# JMDuino_Shield.net
KiCad netlist of a schematic drawn in EAGLE
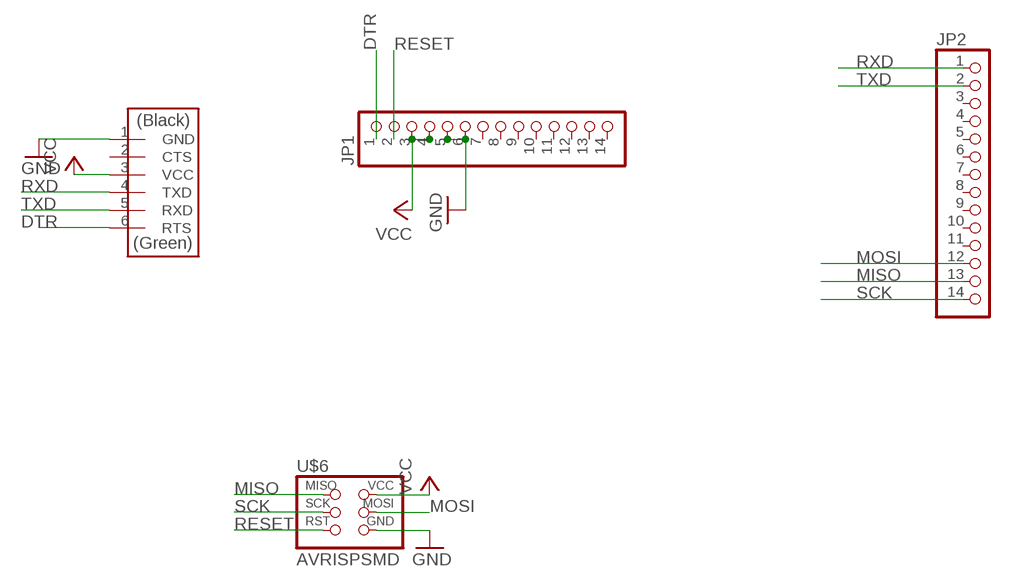
[diagram p0: schematic, sheet 1]

(export (version "E")
  (design (tool "Eeschema 10.0.6"))
  (components
    (comp (ref "JP1")
      (value "PINHD-1X14")
      (footprint "eagle-import:1X14")
      (libsource (lib "eagle-import") (part "PINHD-1X14"))
    )
    (comp (ref "JP2")
      (value "PINHD-1X14")
      (footprint "eagle-import:1X14")
      (libsource (lib "eagle-import") (part "PINHD-1X14"))
    )
    (comp (ref "U$1")
      (value "FTDI-SMD-HEADER")
      (footprint "eagle-import:1X06SMD")
      (libsource (lib "eagle-import") (part "FTDI-SMD-HEADER"))
    )
    (comp (ref "U$6")
      (value "AVRISPSMD")
      (footprint "eagle-import:2X03SMD")
      (libsource (lib "eagle-import") (part "AVRISPSMD"))
    )
  )
  (nets
    (net (code "1") (name "/DTR") (class "Default")
      (node (ref "JP1") (pin "1") (pinfunction "1_1") (pintype "passive"))
      (node (ref "U$1") (pin "6") (pinfunction "RTS_6") (pintype "bidirectional"))
    )
    (net (code "2") (name "/MISO") (class "Default")
      (node (ref "JP2") (pin "13") (pinfunction "13_13") (pintype "passive"))
      (node (ref "U$6") (pin "1") (pinfunction "MISO_1") (pintype "passive"))
    )
    (net (code "3") (name "/MOSI") (class "Default")
      (node (ref "JP2") (pin "12") (pinfunction "12_12") (pintype "passive"))
      (node (ref "U$6") (pin "4") (pinfunction "MOSI_4") (pintype "passive"))
    )
    (net (code "4") (name "/RESET") (class "Default")
      (node (ref "JP1") (pin "2") (pinfunction "2_2") (pintype "passive"))
      (node (ref "U$6") (pin "5") (pinfunction "RST_5") (pintype "passive"))
    )
    (net (code "5") (name "/RXD") (class "Default")
      (node (ref "JP2") (pin "1") (pinfunction "1_1") (pintype "passive"))
      (node (ref "U$1") (pin "4") (pinfunction "TXD_4") (pintype "bidirectional"))
    )
    (net (code "6") (name "/SCK") (class "Default")
      (node (ref "JP2") (pin "14") (pinfunction "14_14") (pintype "passive"))
      (node (ref "U$6") (pin "3") (pinfunction "SCK_3") (pintype "passive"))
    )
    (net (code "7") (name "/TXD") (class "Default")
      (node (ref "JP2") (pin "2") (pinfunction "2_2") (pintype "passive"))
      (node (ref "U$1") (pin "5") (pinfunction "RXD_5") (pintype "bidirectional"))
    )
    (net (code "8") (name "GND") (class "Default")
      (node (ref "JP1") (pin "5") (pinfunction "5_5") (pintype "passive"))
      (node (ref "JP1") (pin "6") (pinfunction "6_6") (pintype "passive"))
      (node (ref "U$1") (pin "1") (pinfunction "GND_1") (pintype "bidirectional"))
      (node (ref "U$6") (pin "6") (pinfunction "GND_6") (pintype "passive"))
    )
    (net (code "9") (name "VCC") (class "Default")
      (node (ref "JP1") (pin "3") (pinfunction "3_3") (pintype "passive"))
      (node (ref "JP1") (pin "4") (pinfunction "4_4") (pintype "passive"))
      (node (ref "U$1") (pin "3") (pinfunction "VCC_3") (pintype "bidirectional"))
      (node (ref "U$6") (pin "2") (pinfunction "VCC_2") (pintype "passive"))
    )
    (net (code "10") (name "unconnected-(JP1-Pad7)") (class "Default")
      (node (ref "JP1") (pin "7") (pinfunction "7_7") (pintype "passive"))
    )
    (net (code "11") (name "unconnected-(JP1-Pad8)") (class "Default")
      (node (ref "JP1") (pin "8") (pinfunction "8_8") (pintype "passive"))
    )
    (net (code "12") (name "unconnected-(JP1-Pad9)") (class "Default")
      (node (ref "JP1") (pin "9") (pinfunction "9_9") (pintype "passive"))
    )
    (net (code "13") (name "unconnected-(JP1-Pad10)") (class "Default")
      (node (ref "JP1") (pin "10") (pinfunction "10_10") (pintype "passive"))
    )
    (net (code "14") (name "unconnected-(JP1-Pad11)") (class "Default")
      (node (ref "JP1") (pin "11") (pinfunction "11_11") (pintype "passive"))
    )
    (net (code "15") (name "unconnected-(JP1-Pad12)") (class "Default")
      (node (ref "JP1") (pin "12") (pinfunction "12_12") (pintype "passive"))
    )
    (net (code "16") (name "unconnected-(JP1-Pad13)") (class "Default")
      (node (ref "JP1") (pin "13") (pinfunction "13_13") (pintype "passive"))
    )
    (net (code "17") (name "unconnected-(JP1-Pad14)") (class "Default")
      (node (ref "JP1") (pin "14") (pinfunction "14_14") (pintype "passive"))
    )
    (net (code "18") (name "unconnected-(JP2-Pad3)") (class "Default")
      (node (ref "JP2") (pin "3") (pinfunction "3_3") (pintype "passive"))
    )
    (net (code "19") (name "unconnected-(JP2-Pad4)") (class "Default")
      (node (ref "JP2") (pin "4") (pinfunction "4_4") (pintype "passive"))
    )
    (net (code "20") (name "unconnected-(JP2-Pad5)") (class "Default")
      (node (ref "JP2") (pin "5") (pinfunction "5_5") (pintype "passive"))
    )
    (net (code "21") (name "unconnected-(JP2-Pad6)") (class "Default")
      (node (ref "JP2") (pin "6") (pinfunction "6_6") (pintype "passive"))
    )
    (net (code "22") (name "unconnected-(JP2-Pad7)") (class "Default")
      (node (ref "JP2") (pin "7") (pinfunction "7_7") (pintype "passive"))
    )
    (net (code "23") (name "unconnected-(JP2-Pad8)") (class "Default")
      (node (ref "JP2") (pin "8") (pinfunction "8_8") (pintype "passive"))
    )
    (net (code "24") (name "unconnected-(JP2-Pad9)") (class "Default")
      (node (ref "JP2") (pin "9") (pinfunction "9_9") (pintype "passive"))
    )
    (net (code "25") (name "unconnected-(JP2-Pad10)") (class "Default")
      (node (ref "JP2") (pin "10") (pinfunction "10_10") (pintype "passive"))
    )
    (net (code "26") (name "unconnected-(JP2-Pad11)") (class "Default")
      (node (ref "JP2") (pin "11") (pinfunction "11_11") (pintype "passive"))
    )
    (net (code "27") (name "unconnected-(U$1-CTS-Pad2)") (class "Default")
      (node (ref "U$1") (pin "2") (pinfunction "CTS_2") (pintype "bidirectional"))
    )
  )
)
